# Keypad_Shield.net
KiCad netlist of a schematic drawn in EAGLE
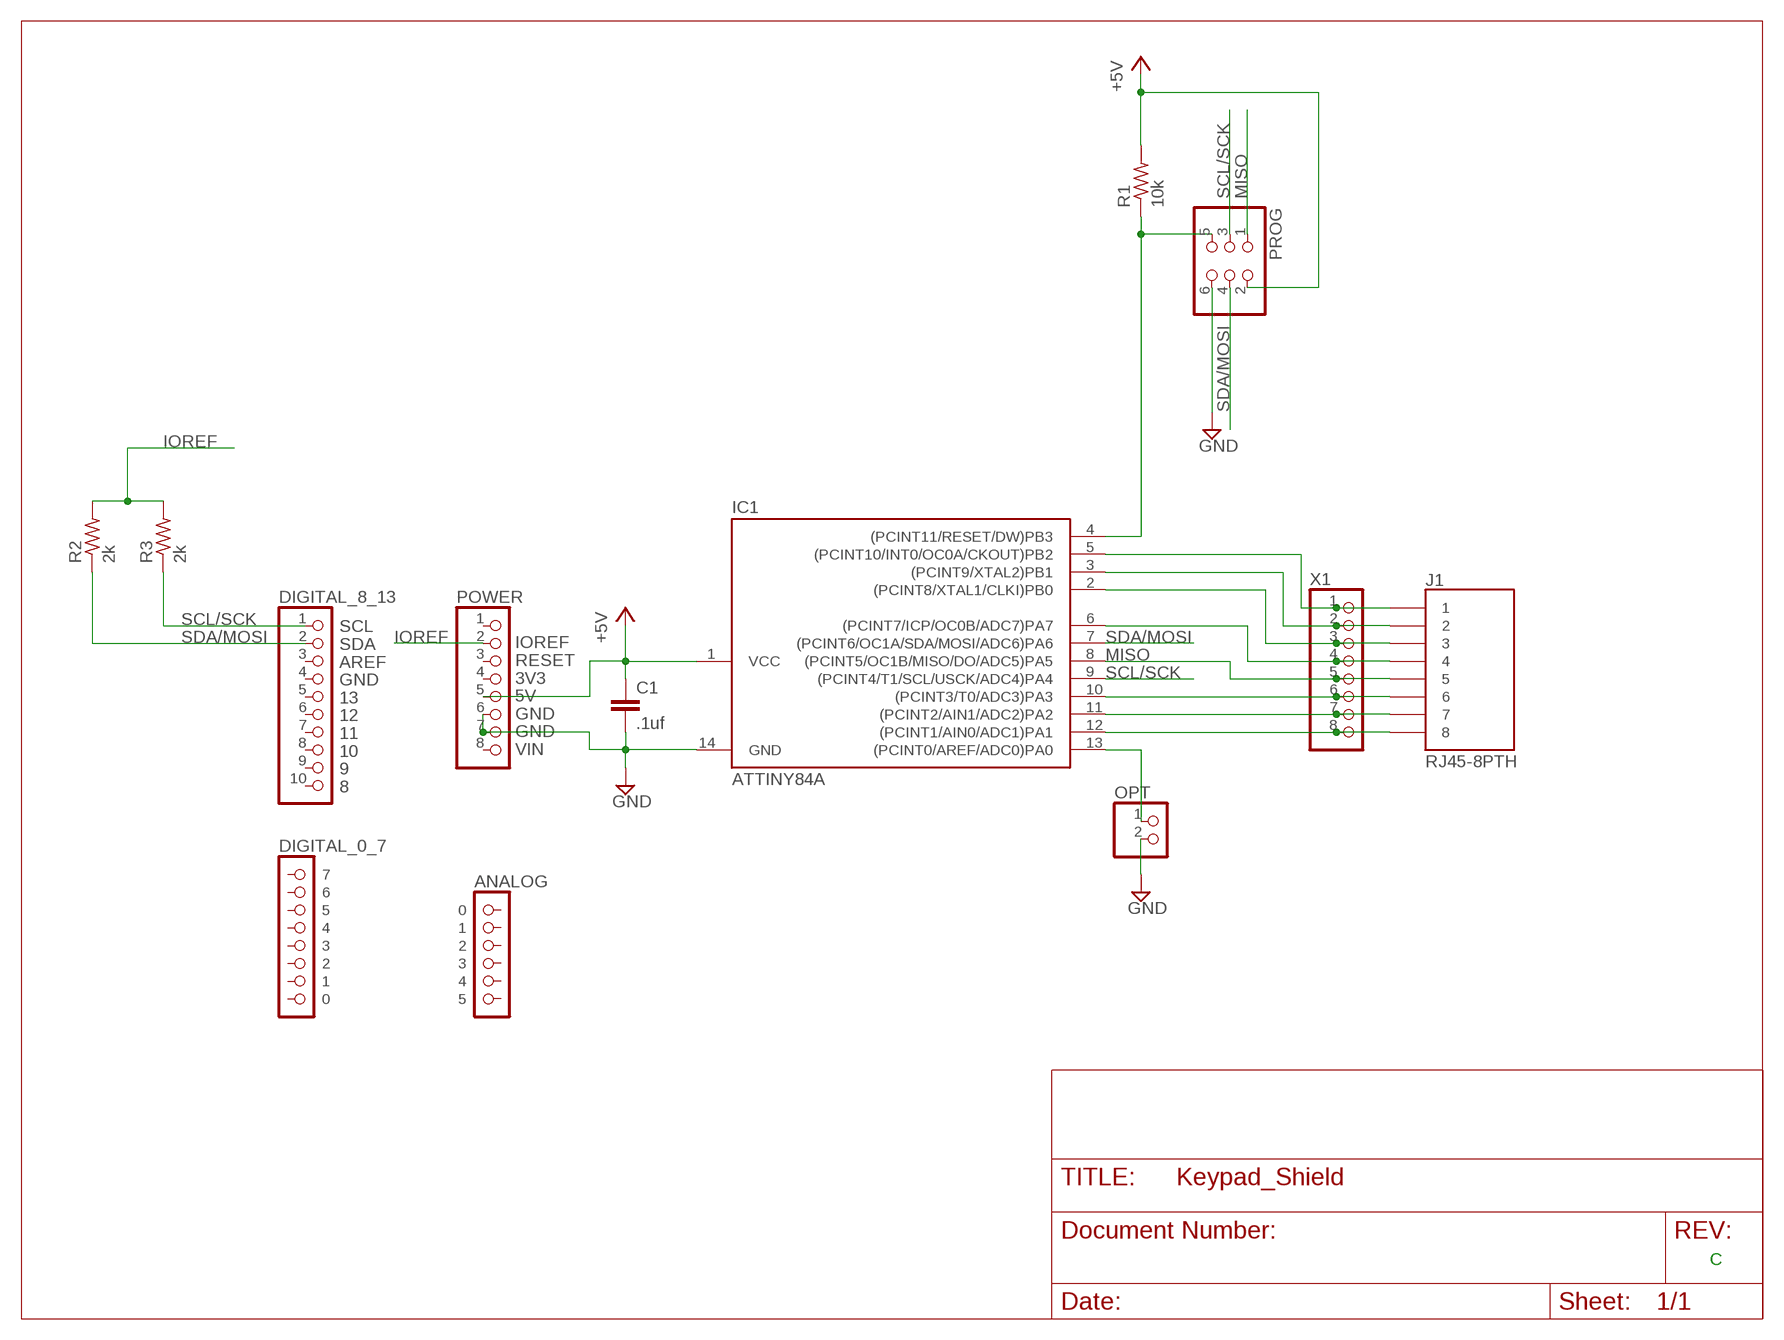
[diagram p0: schematic, sheet 1]

(export (version "E")
  (design (tool "Eeschema 10.0.6"))
  (components
    (comp (ref "C1")
      (value ".1uf")
      (footprint "eagle-import:C5B5")
      (libsource (lib "eagle-import") (part "C5/5"))
    )
    (comp (ref "DIGITAL_8_13")
      (value "PINHD-1X10")
      (footprint "eagle-import:1X10")
      (libsource (lib "eagle-import") (part "PINHD-1X10"))
    )
    (comp (ref "IC1")
      (value "ATTINY84A")
      (footprint "eagle-import:DIL14")
      (libsource (lib "eagle-import") (part "TINY24/44/84-PU"))
    )
    (comp (ref "J1")
      (value "RJ45-8PTH")
      (footprint "eagle-import:RJ45-8")
      (libsource (lib "eagle-import") (part "RJ45-8PTH"))
    )
    (comp (ref "OPT")
      (value "PINHD-1X2")
      (footprint "eagle-import:1X02")
      (libsource (lib "eagle-import") (part "PINHD-1X2"))
    )
    (comp (ref "POWER")
      (value "PINHD-1X8")
      (footprint "eagle-import:1X08")
      (libsource (lib "eagle-import") (part "PINHD-1X8"))
    )
    (comp (ref "PROG")
      (value "PINHD-2X3")
      (footprint "eagle-import:2X03")
      (libsource (lib "eagle-import") (part "PINHD-2X3"))
    )
    (comp (ref "R1")
      (value "10k")
      (footprint "eagle-import:0204_5")
      (libsource (lib "eagle-import") (part "R-US_0204/5"))
    )
    (comp (ref "R2")
      (value "2k")
      (footprint "eagle-import:0204_5")
      (libsource (lib "eagle-import") (part "R-US_0204/5"))
    )
    (comp (ref "R3")
      (value "2k")
      (footprint "eagle-import:0204_5")
      (libsource (lib "eagle-import") (part "R-US_0204/5"))
    )
    (comp (ref "U$2")
      (value "ANALOG")
      (footprint "eagle-import:1X06")
      (libsource (lib "eagle-import") (part "ANALOG"))
    )
    (comp (ref "U$3")
      (value "DIGITAL_0_7")
      (footprint "eagle-import:1X08")
      (libsource (lib "eagle-import") (part "DIGITAL_0_7"))
    )
    (comp (ref "X1")
      (value "HEADER-1X8ROUND")
      (footprint "eagle-import:1X08_ROUND")
      (libsource (lib "eagle-import") (part "HEADER-1X8ROUND"))
    )
  )
  (nets
    (net (code "1") (name "+5V") (class "Default")
      (node (ref "C1") (pin "1") (pinfunction "1_1") (pintype "passive"))
      (node (ref "IC1") (pin "1") (pinfunction "VCC_1") (pintype "power_in"))
      (node (ref "POWER") (pin "5") (pinfunction "5_5") (pintype "passive"))
      (node (ref "PROG") (pin "2") (pinfunction "2_2") (pintype "passive"))
      (node (ref "R1") (pin "2") (pinfunction "2_2") (pintype "passive"))
    )
    (net (code "2") (name "/IOREF") (class "Default")
      (node (ref "POWER") (pin "2") (pinfunction "2_2") (pintype "passive"))
      (node (ref "R2") (pin "2") (pinfunction "2_2") (pintype "passive"))
      (node (ref "R3") (pin "2") (pinfunction "2_2") (pintype "passive"))
    )
    (net (code "3") (name "/MISO") (class "Default")
      (node (ref "IC1") (pin "8") (pinfunction "(PCINT5/OC1B/MISO/DO/ADC5)PA5_8") (pintype "bidirectional"))
      (node (ref "J1") (pin "5") (pinfunction "5_5") (pintype "bidirectional"))
      (node (ref "PROG") (pin "1") (pinfunction "1_1") (pintype "passive"))
      (node (ref "X1") (pin "5") (pinfunction "5_5") (pintype "passive"))
    )
    (net (code "4") (name "/SCL{slash}SCK") (class "Default")
      (node (ref "DIGITAL_8_13") (pin "1") (pinfunction "1_1") (pintype "passive"))
      (node (ref "IC1") (pin "9") (pinfunction "(PCINT4/T1/SCL/USCK/ADC4)PA4_9") (pintype "bidirectional"))
      (node (ref "PROG") (pin "3") (pinfunction "3_3") (pintype "passive"))
      (node (ref "R3") (pin "1") (pinfunction "1_1") (pintype "passive"))
    )
    (net (code "5") (name "/SDA{slash}MOSI") (class "Default")
      (node (ref "DIGITAL_8_13") (pin "2") (pinfunction "2_2") (pintype "passive"))
      (node (ref "IC1") (pin "7") (pinfunction "(PCINT6/OC1A/SDA/MOSI/ADC6)PA6_7") (pintype "bidirectional"))
      (node (ref "PROG") (pin "4") (pinfunction "4_4") (pintype "passive"))
      (node (ref "R2") (pin "1") (pinfunction "1_1") (pintype "passive"))
    )
    (net (code "6") (name "GND") (class "Default")
      (node (ref "C1") (pin "2") (pinfunction "2_2") (pintype "passive"))
      (node (ref "IC1") (pin "14") (pinfunction "GND_14") (pintype "power_in"))
      (node (ref "OPT") (pin "2") (pinfunction "2_2") (pintype "passive"))
      (node (ref "POWER") (pin "6") (pinfunction "6_6") (pintype "passive"))
      (node (ref "POWER") (pin "7") (pinfunction "7_7") (pintype "passive"))
      (node (ref "PROG") (pin "6") (pinfunction "6_6") (pintype "passive"))
    )
    (net (code "7") (name "Net-(IC1-(PCINT0{slash}AREF{slash}ADC0)PA0)") (class "Default")
      (node (ref "IC1") (pin "13") (pinfunction "(PCINT0/AREF/ADC0)PA0_13") (pintype "bidirectional"))
      (node (ref "OPT") (pin "1") (pinfunction "1_1") (pintype "passive"))
    )
    (net (code "8") (name "Net-(IC1-(PCINT1{slash}AIN0{slash}ADC1)PA1)") (class "Default")
      (node (ref "IC1") (pin "12") (pinfunction "(PCINT1/AIN0/ADC1)PA1_12") (pintype "bidirectional"))
      (node (ref "J1") (pin "8") (pinfunction "8_8") (pintype "bidirectional"))
      (node (ref "X1") (pin "8") (pinfunction "8_8") (pintype "passive"))
    )
    (net (code "9") (name "Net-(IC1-(PCINT2{slash}AIN1{slash}ADC2)PA2)") (class "Default")
      (node (ref "IC1") (pin "11") (pinfunction "(PCINT2/AIN1/ADC2)PA2_11") (pintype "bidirectional"))
      (node (ref "J1") (pin "7") (pinfunction "7_7") (pintype "bidirectional"))
      (node (ref "X1") (pin "7") (pinfunction "7_7") (pintype "passive"))
    )
    (net (code "10") (name "Net-(IC1-(PCINT3{slash}T0{slash}ADC3)PA3)") (class "Default")
      (node (ref "IC1") (pin "10") (pinfunction "(PCINT3/T0/ADC3)PA3_10") (pintype "bidirectional"))
      (node (ref "J1") (pin "6") (pinfunction "6_6") (pintype "bidirectional"))
      (node (ref "X1") (pin "6") (pinfunction "6_6") (pintype "passive"))
    )
    (net (code "11") (name "Net-(IC1-(PCINT7{slash}ICP{slash}OC0B{slash}ADC7)PA7)") (class "Default")
      (node (ref "IC1") (pin "6") (pinfunction "(PCINT7/ICP/OC0B/ADC7)PA7_6") (pintype "bidirectional"))
      (node (ref "J1") (pin "4") (pinfunction "4_4") (pintype "bidirectional"))
      (node (ref "X1") (pin "4") (pinfunction "4_4") (pintype "passive"))
    )
    (net (code "12") (name "Net-(IC1-(PCINT8{slash}XTAL1{slash}CLKI)PB0)") (class "Default")
      (node (ref "IC1") (pin "2") (pinfunction "(PCINT8/XTAL1/CLKI)PB0_2") (pintype "bidirectional"))
      (node (ref "J1") (pin "3") (pinfunction "3_3") (pintype "bidirectional"))
      (node (ref "X1") (pin "3") (pinfunction "3_3") (pintype "passive"))
    )
    (net (code "13") (name "Net-(IC1-(PCINT9{slash}XTAL2)PB1)") (class "Default")
      (node (ref "IC1") (pin "3") (pinfunction "(PCINT9/XTAL2)PB1_3") (pintype "bidirectional"))
      (node (ref "J1") (pin "2") (pinfunction "2_2") (pintype "bidirectional"))
      (node (ref "X1") (pin "2") (pinfunction "2_2") (pintype "passive"))
    )
    (net (code "14") (name "Net-(IC1-(PCINT10{slash}INT0{slash}OC0A{slash}CKOUT)PB2)") (class "Default")
      (node (ref "IC1") (pin "5") (pinfunction "(PCINT10/INT0/OC0A/CKOUT)PB2_5") (pintype "bidirectional"))
      (node (ref "J1") (pin "1") (pinfunction "1_1") (pintype "bidirectional"))
      (node (ref "X1") (pin "1") (pinfunction "1_1") (pintype "passive"))
    )
    (net (code "15") (name "Net-(IC1-(PCINT11{slash}RESET{slash}DW)PB3)") (class "Default")
      (node (ref "IC1") (pin "4") (pinfunction "(PCINT11/RESET/DW)PB3_4") (pintype "bidirectional"))
      (node (ref "PROG") (pin "5") (pinfunction "5_5") (pintype "passive"))
      (node (ref "R1") (pin "1") (pinfunction "1_1") (pintype "passive"))
    )
    (net (code "16") (name "unconnected-(DIGITAL_8_13-Pad3)") (class "Default")
      (node (ref "DIGITAL_8_13") (pin "3") (pinfunction "3_3") (pintype "passive"))
    )
    (net (code "17") (name "unconnected-(DIGITAL_8_13-Pad4)") (class "Default")
      (node (ref "DIGITAL_8_13") (pin "4") (pinfunction "4_4") (pintype "passive"))
    )
    (net (code "18") (name "unconnected-(DIGITAL_8_13-Pad5)") (class "Default")
      (node (ref "DIGITAL_8_13") (pin "5") (pinfunction "5_5") (pintype "passive"))
    )
    (net (code "19") (name "unconnected-(DIGITAL_8_13-Pad6)") (class "Default")
      (node (ref "DIGITAL_8_13") (pin "6") (pinfunction "6_6") (pintype "passive"))
    )
    (net (code "20") (name "unconnected-(DIGITAL_8_13-Pad7)") (class "Default")
      (node (ref "DIGITAL_8_13") (pin "7") (pinfunction "7_7") (pintype "passive"))
    )
    (net (code "21") (name "unconnected-(DIGITAL_8_13-Pad8)") (class "Default")
      (node (ref "DIGITAL_8_13") (pin "8") (pinfunction "8_8") (pintype "passive"))
    )
    (net (code "22") (name "unconnected-(DIGITAL_8_13-Pad9)") (class "Default")
      (node (ref "DIGITAL_8_13") (pin "9") (pinfunction "9_9") (pintype "passive"))
    )
    (net (code "23") (name "unconnected-(DIGITAL_8_13-Pad10)") (class "Default")
      (node (ref "DIGITAL_8_13") (pin "10") (pinfunction "10_10") (pintype "passive"))
    )
    (net (code "24") (name "unconnected-(POWER-Pad1)") (class "Default")
      (node (ref "POWER") (pin "1") (pinfunction "1_1") (pintype "passive"))
    )
    (net (code "25") (name "unconnected-(POWER-Pad3)") (class "Default")
      (node (ref "POWER") (pin "3") (pinfunction "3_3") (pintype "passive"))
    )
    (net (code "26") (name "unconnected-(POWER-Pad4)") (class "Default")
      (node (ref "POWER") (pin "4") (pinfunction "4_4") (pintype "passive"))
    )
    (net (code "27") (name "unconnected-(POWER-Pad8)") (class "Default")
      (node (ref "POWER") (pin "8") (pinfunction "8_8") (pintype "passive"))
    )
    (net (code "28") (name "unconnected-(U$2-0-Pad1)") (class "Default")
      (node (ref "U$2") (pin "1") (pinfunction "0_1") (pintype "passive"))
    )
    (net (code "29") (name "unconnected-(U$2-1-Pad2)") (class "Default")
      (node (ref "U$2") (pin "2") (pinfunction "1_2") (pintype "passive"))
    )
    (net (code "30") (name "unconnected-(U$2-2-Pad3)") (class "Default")
      (node (ref "U$2") (pin "3") (pinfunction "2_3") (pintype "passive"))
    )
    (net (code "31") (name "unconnected-(U$2-3-Pad4)") (class "Default")
      (node (ref "U$2") (pin "4") (pinfunction "3_4") (pintype "passive"))
    )
    (net (code "32") (name "unconnected-(U$2-4-Pad5)") (class "Default")
      (node (ref "U$2") (pin "5") (pinfunction "4_5") (pintype "passive"))
    )
    (net (code "33") (name "unconnected-(U$2-5-Pad6)") (class "Default")
      (node (ref "U$2") (pin "6") (pinfunction "5_6") (pintype "passive"))
    )
    (net (code "34") (name "unconnected-(U$3-0-Pad8)") (class "Default")
      (node (ref "U$3") (pin "8") (pinfunction "0_8") (pintype "passive"))
    )
    (net (code "35") (name "unconnected-(U$3-1-Pad7)") (class "Default")
      (node (ref "U$3") (pin "7") (pinfunction "1_7") (pintype "passive"))
    )
    (net (code "36") (name "unconnected-(U$3-2-Pad6)") (class "Default")
      (node (ref "U$3") (pin "6") (pinfunction "2_6") (pintype "passive"))
    )
    (net (code "37") (name "unconnected-(U$3-3-Pad5)") (class "Default")
      (node (ref "U$3") (pin "5") (pinfunction "3_5") (pintype "passive"))
    )
    (net (code "38") (name "unconnected-(U$3-5-Pad3)") (class "Default")
      (node (ref "U$3") (pin "3") (pinfunction "5_3") (pintype "passive"))
    )
    (net (code "39") (name "unconnected-(U$3-6-Pad2)") (class "Default")
      (node (ref "U$3") (pin "2") (pinfunction "6_2") (pintype "passive"))
    )
    (net (code "40") (name "unconnected-(U$3-7-Pad1)") (class "Default")
      (node (ref "U$3") (pin "1") (pinfunction "7_1") (pintype "passive"))
    )
    (net (code "41") (name "unconnected-(U$3-Pad4)") (class "Default")
      (node (ref "U$3") (pin "4") (pinfunction "4_4") (pintype "passive"))
    )
  )
)
